# pll_schematic_temp.net
KiCad netlist of a schematic drawn in Altium Designer
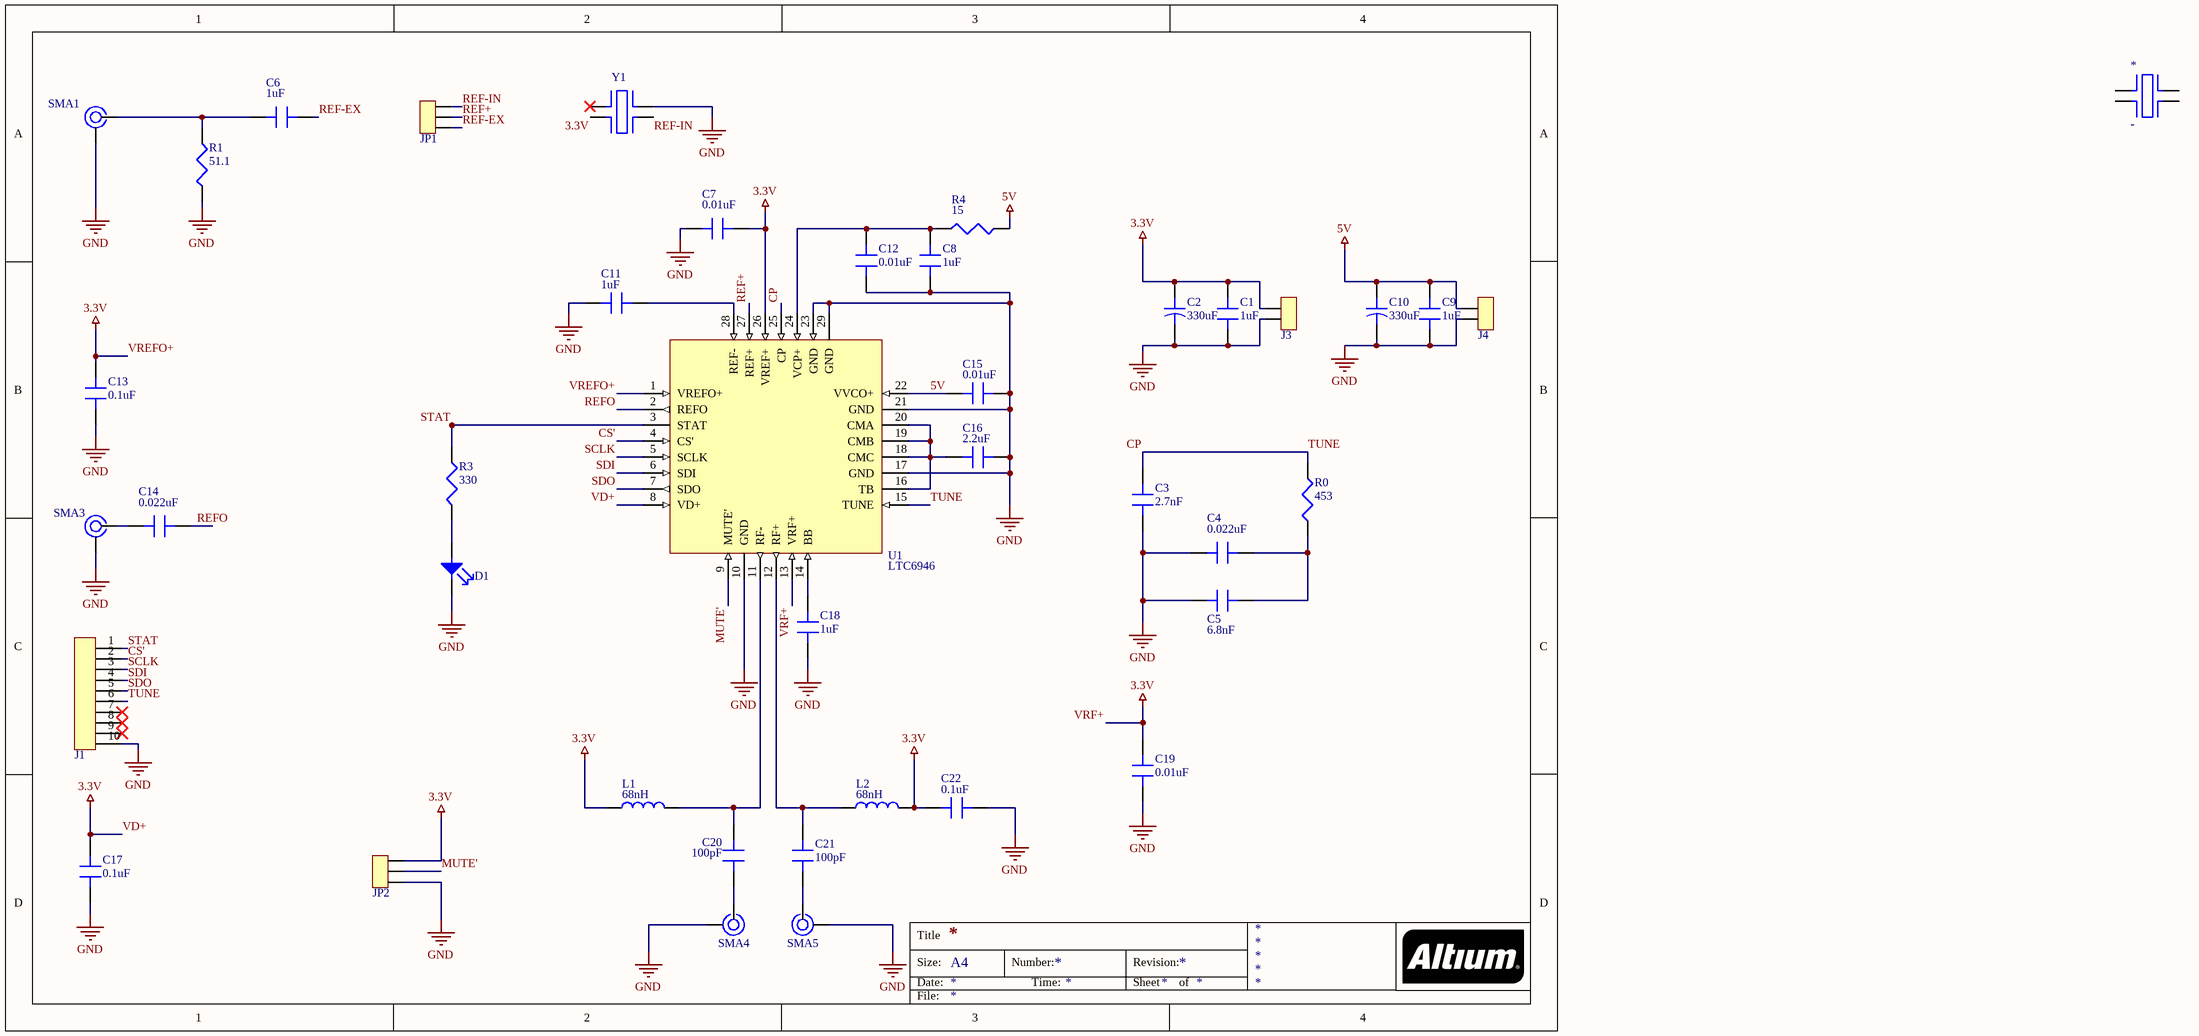
[diagram p0: pll_schematic_temp.SchDoc]

(export (version "E")
  (design (tool "Eeschema 10.0.6"))
  (components
    (comp (ref "*") (value "-") (libsource (lib "pll_schematic_lib") (part "OSC")))
    (comp (ref "C1") (value "1uF") (libsource (lib "pll_schematic_lib") (part "C")))
    (comp (ref "C2") (value "330uF") (libsource (lib "pll_schematic_lib") (part "CP")))
    (comp (ref "C3") (value "2.7nF") (libsource (lib "pll_schematic_lib") (part "C")))
    (comp (ref "C4") (value "0.022uF") (libsource (lib "pll_schematic_lib") (part "C")))
    (comp (ref "C5") (value "6.8nF") (libsource (lib "pll_schematic_lib") (part "C")))
    (comp (ref "C6") (value "1uF") (libsource (lib "pll_schematic_lib") (part "C")))
    (comp (ref "C7") (value "0.01uF") (libsource (lib "pll_schematic_lib") (part "C")))
    (comp (ref "C8") (value "1uF") (libsource (lib "pll_schematic_lib") (part "C")))
    (comp (ref "C9") (value "1uF") (libsource (lib "pll_schematic_lib") (part "C")))
    (comp (ref "C10") (value "330uF") (libsource (lib "pll_schematic_lib") (part "CP")))
    (comp (ref "C11") (value "1uF") (libsource (lib "pll_schematic_lib") (part "C")))
    (comp (ref "C12") (value "0.01uF") (libsource (lib "pll_schematic_lib") (part "C")))
    (comp (ref "C13") (value "0.1uF") (libsource (lib "pll_schematic_lib") (part "C")))
    (comp (ref "C14") (value "0.022uF") (libsource (lib "pll_schematic_lib") (part "C")))
    (comp (ref "C15") (value "0.01uF") (libsource (lib "pll_schematic_lib") (part "C")))
    (comp (ref "C16") (value "2.2uF") (libsource (lib "pll_schematic_lib") (part "C")))
    (comp (ref "C17") (value "0.1uF") (libsource (lib "pll_schematic_lib") (part "C")))
    (comp (ref "C18") (value "1uF") (libsource (lib "pll_schematic_lib") (part "C")))
    (comp (ref "C19") (value "0.01uF") (libsource (lib "pll_schematic_lib") (part "C")))
    (comp (ref "C20") (value "100pF") (libsource (lib "pll_schematic_lib") (part "C")))
    (comp (ref "C21") (value "100pF") (libsource (lib "pll_schematic_lib") (part "C")))
    (comp (ref "C22") (value "0.1uF") (libsource (lib "pll_schematic_lib") (part "C")))
    (comp (ref "D1") (value "-") (libsource (lib "pll_schematic_lib") (part "LED")))
    (comp (ref "J1")
      (value "-")
      (footprint "ACS770")
      (libsource (lib "pll_schematic_lib") (part "Conn_Gene_1x10"))
    )
    (comp (ref "J3") (value "-") (libsource (lib "pll_schematic_lib") (part "Conn_Gene_1x02")))
    (comp (ref "J4") (value "-") (libsource (lib "pll_schematic_lib") (part "Conn_Gene_1x02")))
    (comp (ref "JP1")
      (value "-")
      (footprint "ACS770")
      (libsource (lib "pll_schematic_lib") (part "Pin Header 1x03"))
    )
    (comp (ref "JP2")
      (value "-")
      (footprint "ACS770")
      (libsource (lib "pll_schematic_lib") (part "Pin Header 1x03"))
    )
    (comp (ref "L1") (value "68nH") (libsource (lib "pll_schematic_lib") (part "L")))
    (comp (ref "L2") (value "68nH") (libsource (lib "pll_schematic_lib") (part "L")))
    (comp (ref "R0") (value "453") (libsource (lib "pll_schematic_lib") (part "R")))
    (comp (ref "R1") (value "51.1") (libsource (lib "pll_schematic_lib") (part "R")))
    (comp (ref "R3") (value "330") (libsource (lib "pll_schematic_lib") (part "R")))
    (comp (ref "R4") (value "15") (libsource (lib "pll_schematic_lib") (part "R")))
    (comp (ref "SMA1") (value "-") (libsource (lib "pll_schematic_lib") (part "SMA")))
    (comp (ref "SMA3") (value "-") (libsource (lib "pll_schematic_lib") (part "SMA")))
    (comp (ref "SMA4") (value "-") (libsource (lib "") (part "SMA_1")))
    (comp (ref "SMA5") (value "-") (libsource (lib "pll_schematic_lib") (part "SMA")))
    (comp (ref "U1") (value "LTC6946") (libsource (lib "pll_schematic_lib") (part "LTC6946IUFD-1#PBF-ND")))
    (comp (ref "Y1") (value "-") (libsource (lib "pll_schematic_lib") (part "OSC")))
  )
  (nets
    (net (code "1") (name "/CP") (class "Default")
      (node (ref "C3") (pin "2") (pinfunction "-_2") (pintype "passive"))
      (node (ref "J1") (pin "6") (pinfunction "*_6") (pintype "passive"))
      (node (ref "R0") (pin "2") (pinfunction "-_2") (pintype "passive"))
      (node (ref "U1") (pin "15") (pinfunction "TUNE_15") (pintype "input"))
      (node (ref "U1") (pin "25") (pinfunction "CP_25") (pintype "input"))
    )
    (net (code "2") (name "/CS'") (class "Default")
      (node (ref "J1") (pin "2") (pinfunction "*_2") (pintype "passive"))
      (node (ref "U1") (pin "4") (pinfunction "CS'_4") (pintype "input"))
    )
    (net (code "3") (name "/MUTE'") (class "Default")
      (node (ref "JP2") (pin "2") (pinfunction "-_2") (pintype "passive"))
      (node (ref "U1") (pin "9") (pinfunction "MUTE'_9") (pintype "input"))
    )
    (net (code "4") (name "/REF+") (class "Default")
      (node (ref "JP1") (pin "2") (pinfunction "-_2") (pintype "passive"))
      (node (ref "U1") (pin "27") (pinfunction "REF+_27") (pintype "input"))
    )
    (net (code "5") (name "/REF-EX") (class "Default")
      (node (ref "C6") (pin "2") (pinfunction "-_2") (pintype "passive"))
      (node (ref "JP1") (pin "3") (pinfunction "-_3") (pintype "passive"))
    )
    (net (code "6") (name "/REF-IN") (class "Default")
      (node (ref "JP1") (pin "1") (pinfunction "-_1") (pintype "passive"))
      (node (ref "Y1") (pin "*") (pinfunction "*_*") (pintype "passive"))
    )
    (net (code "7") (name "/REFO") (class "Default")
      (node (ref "C14") (pin "2") (pinfunction "-_2") (pintype "passive"))
      (node (ref "U1") (pin "2") (pinfunction "REFO_2") (pintype "output"))
    )
    (net (code "8") (name "/SCLK") (class "Default")
      (node (ref "J1") (pin "3") (pinfunction "*_3") (pintype "passive"))
      (node (ref "U1") (pin "5") (pinfunction "SCLK_5") (pintype "input"))
    )
    (net (code "9") (name "/SDI") (class "Default")
      (node (ref "J1") (pin "4") (pinfunction "*_4") (pintype "passive"))
      (node (ref "U1") (pin "6") (pinfunction "SDI_6") (pintype "input"))
    )
    (net (code "10") (name "/SDO") (class "Default")
      (node (ref "J1") (pin "5") (pinfunction "*_5") (pintype "passive"))
      (node (ref "U1") (pin "7") (pinfunction "SDO_7") (pintype "output"))
    )
    (net (code "11") (name "/STAT") (class "Default")
      (node (ref "J1") (pin "1") (pinfunction "*_1") (pintype "passive"))
      (node (ref "R3") (pin "2") (pinfunction "-_2") (pintype "passive"))
      (node (ref "U1") (pin "3") (pinfunction "STAT_3") (pintype "passive"))
    )
    (net (code "12") (name "3.3V") (class "Default")
      (node (ref "C1") (pin "2") (pinfunction "-_2") (pintype "passive"))
      (node (ref "C13") (pin "2") (pinfunction "-_2") (pintype "passive"))
      (node (ref "C17") (pin "2") (pinfunction "-_2") (pintype "passive"))
      (node (ref "C19") (pin "2") (pinfunction "-_2") (pintype "passive"))
      (node (ref "C2") (pin "1") (pinfunction "-_1") (pintype "passive"))
      (node (ref "C22") (pin "1") (pinfunction "-_1") (pintype "passive"))
      (node (ref "C7") (pin "1") (pinfunction "-_1") (pintype "passive"))
      (node (ref "J3") (pin "1") (pinfunction "-_1") (pintype "passive"))
      (node (ref "JP2") (pin "1") (pinfunction "-_1") (pintype "passive"))
      (node (ref "L1") (pin "1") (pinfunction "-_1") (pintype "passive"))
      (node (ref "L2") (pin "2") (pinfunction "-_2") (pintype "passive"))
      (node (ref "U1") (pin "1") (pinfunction "VREFO+_1") (pintype "input"))
      (node (ref "U1") (pin "13") (pinfunction "VRF+_13") (pintype "input"))
      (node (ref "U1") (pin "26") (pinfunction "VREF+_26") (pintype "input"))
      (node (ref "U1") (pin "8") (pinfunction "VD+_8") (pintype "input"))
      (node (ref "Y1") (pin "*") (pinfunction "*_*") (pintype "passive"))
    )
    (net (code "13") (name "5V") (class "Default")
      (node (ref "C10") (pin "1") (pinfunction "-_1") (pintype "passive"))
      (node (ref "C15") (pin "1") (pinfunction "-_1") (pintype "passive"))
      (node (ref "C9") (pin "1") (pinfunction "-_1") (pintype "passive"))
      (node (ref "J4") (pin "1") (pinfunction "-_1") (pintype "passive"))
      (node (ref "R4") (pin "2") (pinfunction "-_2") (pintype "passive"))
      (node (ref "U1") (pin "22") (pinfunction "VVCO+_22") (pintype "input"))
    )
    (net (code "14") (name "GND") (class "Default")
      (node (ref "C1") (pin "1") (pinfunction "-_1") (pintype "passive"))
      (node (ref "C10") (pin "2") (pinfunction "-_2") (pintype "passive"))
      (node (ref "C11") (pin "1") (pinfunction "-_1") (pintype "passive"))
      (node (ref "C12") (pin "2") (pinfunction "-_2") (pintype "passive"))
      (node (ref "C13") (pin "1") (pinfunction "-_1") (pintype "passive"))
      (node (ref "C15") (pin "2") (pinfunction "-_2") (pintype "passive"))
      (node (ref "C16") (pin "2") (pinfunction "-_2") (pintype "passive"))
      (node (ref "C17") (pin "1") (pinfunction "-_1") (pintype "passive"))
      (node (ref "C18") (pin "1") (pinfunction "-_1") (pintype "passive"))
      (node (ref "C19") (pin "1") (pinfunction "-_1") (pintype "passive"))
      (node (ref "C2") (pin "2") (pinfunction "-_2") (pintype "passive"))
      (node (ref "C22") (pin "2") (pinfunction "-_2") (pintype "passive"))
      (node (ref "C3") (pin "1") (pinfunction "-_1") (pintype "passive"))
      (node (ref "C4") (pin "2") (pinfunction "-_2") (pintype "passive"))
      (node (ref "C5") (pin "2") (pinfunction "-_2") (pintype "passive"))
      (node (ref "C7") (pin "2") (pinfunction "-_2") (pintype "passive"))
      (node (ref "C8") (pin "1") (pinfunction "-_1") (pintype "passive"))
      (node (ref "C9") (pin "2") (pinfunction "-_2") (pintype "passive"))
      (node (ref "D1") (pin "2") (pinfunction "-_2") (pintype "passive"))
      (node (ref "J1") (pin "10") (pinfunction "*_10") (pintype "passive"))
      (node (ref "J3") (pin "2") (pinfunction "-_2") (pintype "passive"))
      (node (ref "J4") (pin "2") (pinfunction "-_2") (pintype "passive"))
      (node (ref "JP2") (pin "3") (pinfunction "-_3") (pintype "passive"))
      (node (ref "R1") (pin "1") (pinfunction "-_1") (pintype "passive"))
      (node (ref "SMA1") (pin "2") (pinfunction "-_2") (pintype "passive"))
      (node (ref "SMA3") (pin "2") (pinfunction "-_2") (pintype "passive"))
      (node (ref "SMA4") (pin "2") (pinfunction "-_2") (pintype "passive"))
      (node (ref "SMA5") (pin "2") (pinfunction "-_2") (pintype "passive"))
      (node (ref "U1") (pin "10") (pinfunction "GND_10") (pintype "passive"))
      (node (ref "U1") (pin "17") (pinfunction "GND_17") (pintype "passive"))
      (node (ref "U1") (pin "21") (pinfunction "GND_21") (pintype "passive"))
      (node (ref "U1") (pin "23") (pinfunction "GND_23") (pintype "input"))
      (node (ref "U1") (pin "29") (pinfunction "GND_29") (pintype "passive"))
      (node (ref "Y1") (pin "*") (pinfunction "*_*") (pintype "passive"))
    )
    (net (code "15") (name "Net-(C4---Pad1)") (class "Default")
      (node (ref "C4") (pin "1") (pinfunction "-_1") (pintype "passive"))
      (node (ref "C5") (pin "1") (pinfunction "-_1") (pintype "passive"))
      (node (ref "R0") (pin "1") (pinfunction "-_1") (pintype "passive"))
    )
    (net (code "16") (name "Net-(C6---Pad1)") (class "Default")
      (node (ref "C6") (pin "1") (pinfunction "-_1") (pintype "passive"))
      (node (ref "R1") (pin "2") (pinfunction "-_2") (pintype "passive"))
      (node (ref "SMA1") (pin "1") (pinfunction "-_1") (pintype "passive"))
    )
    (net (code "17") (name "Net-(C14---Pad1)") (class "Default")
      (node (ref "C14") (pin "1") (pinfunction "-_1") (pintype "passive"))
      (node (ref "SMA3") (pin "1") (pinfunction "-_1") (pintype "passive"))
    )
    (net (code "18") (name "Net-(C20---Pad1)") (class "Default")
      (node (ref "C20") (pin "1") (pinfunction "-_1") (pintype "passive"))
      (node (ref "SMA4") (pin "1") (pinfunction "-_1") (pintype "passive"))
    )
    (net (code "19") (name "Net-(C21---Pad1)") (class "Default")
      (node (ref "C21") (pin "1") (pinfunction "-_1") (pintype "passive"))
      (node (ref "SMA5") (pin "1") (pinfunction "-_1") (pintype "passive"))
    )
    (net (code "20") (name "Net-(D1---Pad1)") (class "Default")
      (node (ref "D1") (pin "1") (pinfunction "-_1") (pintype "passive"))
      (node (ref "R3") (pin "1") (pinfunction "-_1") (pintype "passive"))
    )
    (net (code "21") (name "Net-(U1-BB)") (class "Default")
      (node (ref "C18") (pin "2") (pinfunction "-_2") (pintype "passive"))
      (node (ref "U1") (pin "14") (pinfunction "BB_14") (pintype "input"))
    )
    (net (code "22") (name "Net-(U1-CMA)") (class "Default")
      (node (ref "C16") (pin "1") (pinfunction "-_1") (pintype "passive"))
      (node (ref "U1") (pin "16") (pinfunction "TB_16") (pintype "passive"))
      (node (ref "U1") (pin "18") (pinfunction "CMC_18") (pintype "passive"))
      (node (ref "U1") (pin "19") (pinfunction "CMB_19") (pintype "passive"))
      (node (ref "U1") (pin "20") (pinfunction "CMA_20") (pintype "passive"))
    )
    (net (code "23") (name "Net-(U1-REF-)") (class "Default")
      (node (ref "C11") (pin "2") (pinfunction "-_2") (pintype "passive"))
      (node (ref "U1") (pin "28") (pinfunction "REF-_28") (pintype "input"))
    )
    (net (code "24") (name "Net-(U1-RF+)") (class "Default")
      (node (ref "C21") (pin "2") (pinfunction "-_2") (pintype "passive"))
      (node (ref "L2") (pin "1") (pinfunction "-_1") (pintype "passive"))
      (node (ref "U1") (pin "12") (pinfunction "RF+_12") (pintype "output"))
    )
    (net (code "25") (name "Net-(U1-RF-)") (class "Default")
      (node (ref "C20") (pin "2") (pinfunction "-_2") (pintype "passive"))
      (node (ref "L1") (pin "2") (pinfunction "-_2") (pintype "passive"))
      (node (ref "U1") (pin "11") (pinfunction "RF-_11") (pintype "output"))
    )
    (net (code "26") (name "Net-(U1-VCP+)") (class "Default")
      (node (ref "C12") (pin "1") (pinfunction "-_1") (pintype "passive"))
      (node (ref "C8") (pin "2") (pinfunction "-_2") (pintype "passive"))
      (node (ref "R4") (pin "1") (pinfunction "-_1") (pintype "passive"))
      (node (ref "U1") (pin "24") (pinfunction "VCP+_24") (pintype "input"))
    )
    (net (code "27") (name "unconnected-(*-Pad*)") (class "Default")
      (node (ref "*") (pin "*") (pinfunction "*_*") (pintype "passive"))
    )
    (net (code "28") (name "unconnected-(*-Pad*)_1") (class "Default")
      (node (ref "*") (pin "*") (pinfunction "*_*") (pintype "passive"))
    )
    (net (code "29") (name "unconnected-(*-Pad*)_2") (class "Default")
      (node (ref "*") (pin "*") (pinfunction "*_*") (pintype "passive"))
    )
    (net (code "30") (name "unconnected-(*-Pad*)_3") (class "Default")
      (node (ref "*") (pin "*") (pinfunction "*_*") (pintype "passive"))
    )
    (net (code "31") (name "unconnected-(J1-*-Pad7)") (class "Default")
      (node (ref "J1") (pin "7") (pinfunction "*_7") (pintype "passive+no_connect"))
    )
    (net (code "32") (name "unconnected-(J1-*-Pad8)") (class "Default")
      (node (ref "J1") (pin "8") (pinfunction "*_8") (pintype "passive+no_connect"))
    )
    (net (code "33") (name "unconnected-(J1-*-Pad9)") (class "Default")
      (node (ref "J1") (pin "9") (pinfunction "*_9") (pintype "passive+no_connect"))
    )
    (net (code "34") (name "unconnected-(Y1-Pad*)") (class "Default")
      (node (ref "Y1") (pin "*") (pinfunction "*_*") (pintype "passive+no_connect"))
    )
  )
)
